# RS485.net
KiCad netlist of a schematic drawn in Altium Designer
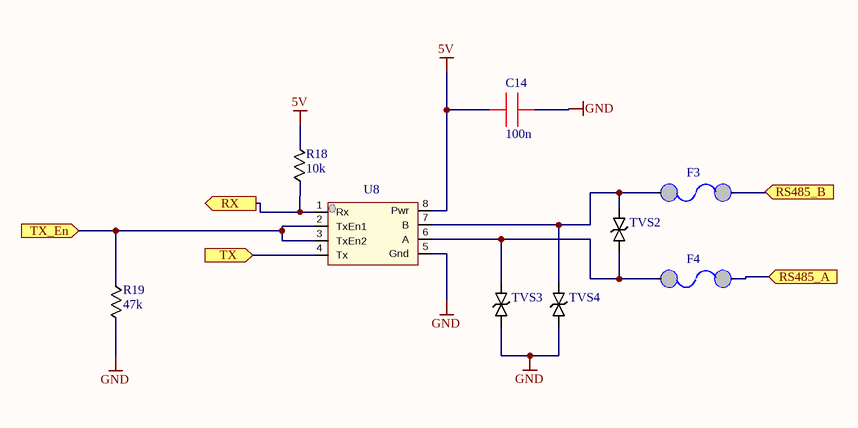
[diagram p0: RS485.SchDoc]

(export (version "E")
  (design (tool "Eeschema 10.0.6"))
  (components
    (comp (ref "C14")
      (value "100n")
      (footprint "0603")
      (description "CC0603KRX7R9BB104")
      (libsource (lib "kontr") (part "0603 CAP"))
    )
    (comp (ref "F3")
      (value "Resettable FUSE")
      (footprint "1210")
      (description "MF-USMF005-2")
      (libsource (lib "kontr") (part "Fuse PTS"))
    )
    (comp (ref "F4")
      (value "Resettable FUSE")
      (footprint "1210")
      (description "MF-USMF005-2")
      (libsource (lib "kontr") (part "Fuse PTS"))
    )
    (comp (ref "R18")
      (value "10k")
      (footprint "0603")
      (description "RC0603FR-0710KL")
      (libsource (lib "kontr") (part "0603 RES"))
    )
    (comp (ref "R19")
      (value "47k")
      (footprint "0603")
      (description "RC0603FR-0747KL")
      (libsource (lib "kontr") (part "0603 RES"))
    )
    (comp (ref "TVS2")
      (value "TVS 6V")
      (footprint "DO-214AC")
      (description "SMAJ6.0CA")
      (libsource (lib "kontr") (part "TVS"))
    )
    (comp (ref "TVS3")
      (value "TVS 6V")
      (footprint "DO-214AC")
      (description "SMAJ6.0CA")
      (libsource (lib "kontr") (part "TVS"))
    )
    (comp (ref "TVS4")
      (value "TVS 6V")
      (footprint "DO-214AC")
      (description "SMAJ6.0CA")
      (libsource (lib "kontr") (part "TVS"))
    )
    (comp (ref "U8")
      (value "RS485 Driver")
      (footprint "SOIC 8")
      (description "SN65HVD3082EDR")
      (libsource (lib "kontr") (part "MAX485"))
    )
  )
  (nets
    (net (code "1") (name "/RS485_A") (class "Default")
      (node (ref "F4") (pin "1") (pinfunction "1_1") (pintype "passive"))
    )
    (net (code "2") (name "/RS485_B") (class "Default")
      (node (ref "F3") (pin "1") (pinfunction "1_1") (pintype "passive"))
    )
    (net (code "3") (name "/RX") (class "Default")
      (node (ref "R18") (pin "1") (pintype "passive"))
      (node (ref "U8") (pin "1") (pinfunction "Rx_1") (pintype "passive"))
    )
    (net (code "4") (name "/TX") (class "Default")
      (node (ref "U8") (pin "4") (pinfunction "Tx_4") (pintype "passive"))
    )
    (net (code "5") (name "/TX_En") (class "Default")
      (node (ref "R19") (pin "1") (pintype "passive"))
      (node (ref "U8") (pin "2") (pinfunction "TxEn1_2") (pintype "passive"))
      (node (ref "U8") (pin "3") (pinfunction "TxEn2_3") (pintype "passive"))
    )
    (net (code "6") (name "5V") (class "Default")
      (node (ref "C14") (pin "1") (pinfunction "1_1") (pintype "passive"))
      (node (ref "R18") (pin "2") (pintype "passive"))
      (node (ref "U8") (pin "8") (pinfunction "Pwr_8") (pintype "passive"))
    )
    (net (code "7") (name "GND") (class "Default")
      (node (ref "C14") (pin "2") (pinfunction "2_2") (pintype "passive"))
      (node (ref "R19") (pin "2") (pintype "passive"))
      (node (ref "TVS3") (pin "1") (pinfunction "1_1") (pintype "passive"))
      (node (ref "TVS4") (pin "1") (pinfunction "1_1") (pintype "passive"))
      (node (ref "U8") (pin "5") (pinfunction "Gnd_5") (pintype "passive"))
    )
    (net (code "8") (name "Net-(U8-A)") (class "Default")
      (node (ref "F4") (pin "2") (pinfunction "2_2") (pintype "passive"))
      (node (ref "TVS2") (pin "1") (pinfunction "1_1") (pintype "passive"))
      (node (ref "TVS3") (pin "2") (pinfunction "2_2") (pintype "passive"))
      (node (ref "U8") (pin "6") (pinfunction "A_6") (pintype "passive"))
    )
    (net (code "9") (name "Net-(U8-B)") (class "Default")
      (node (ref "F3") (pin "2") (pinfunction "2_2") (pintype "passive"))
      (node (ref "TVS2") (pin "2") (pinfunction "2_2") (pintype "passive"))
      (node (ref "TVS4") (pin "2") (pinfunction "2_2") (pintype "passive"))
      (node (ref "U8") (pin "7") (pinfunction "B_7") (pintype "passive"))
    )
  )
)
